# peripheral.net
KiCad netlist of a schematic drawn in Altium Designer
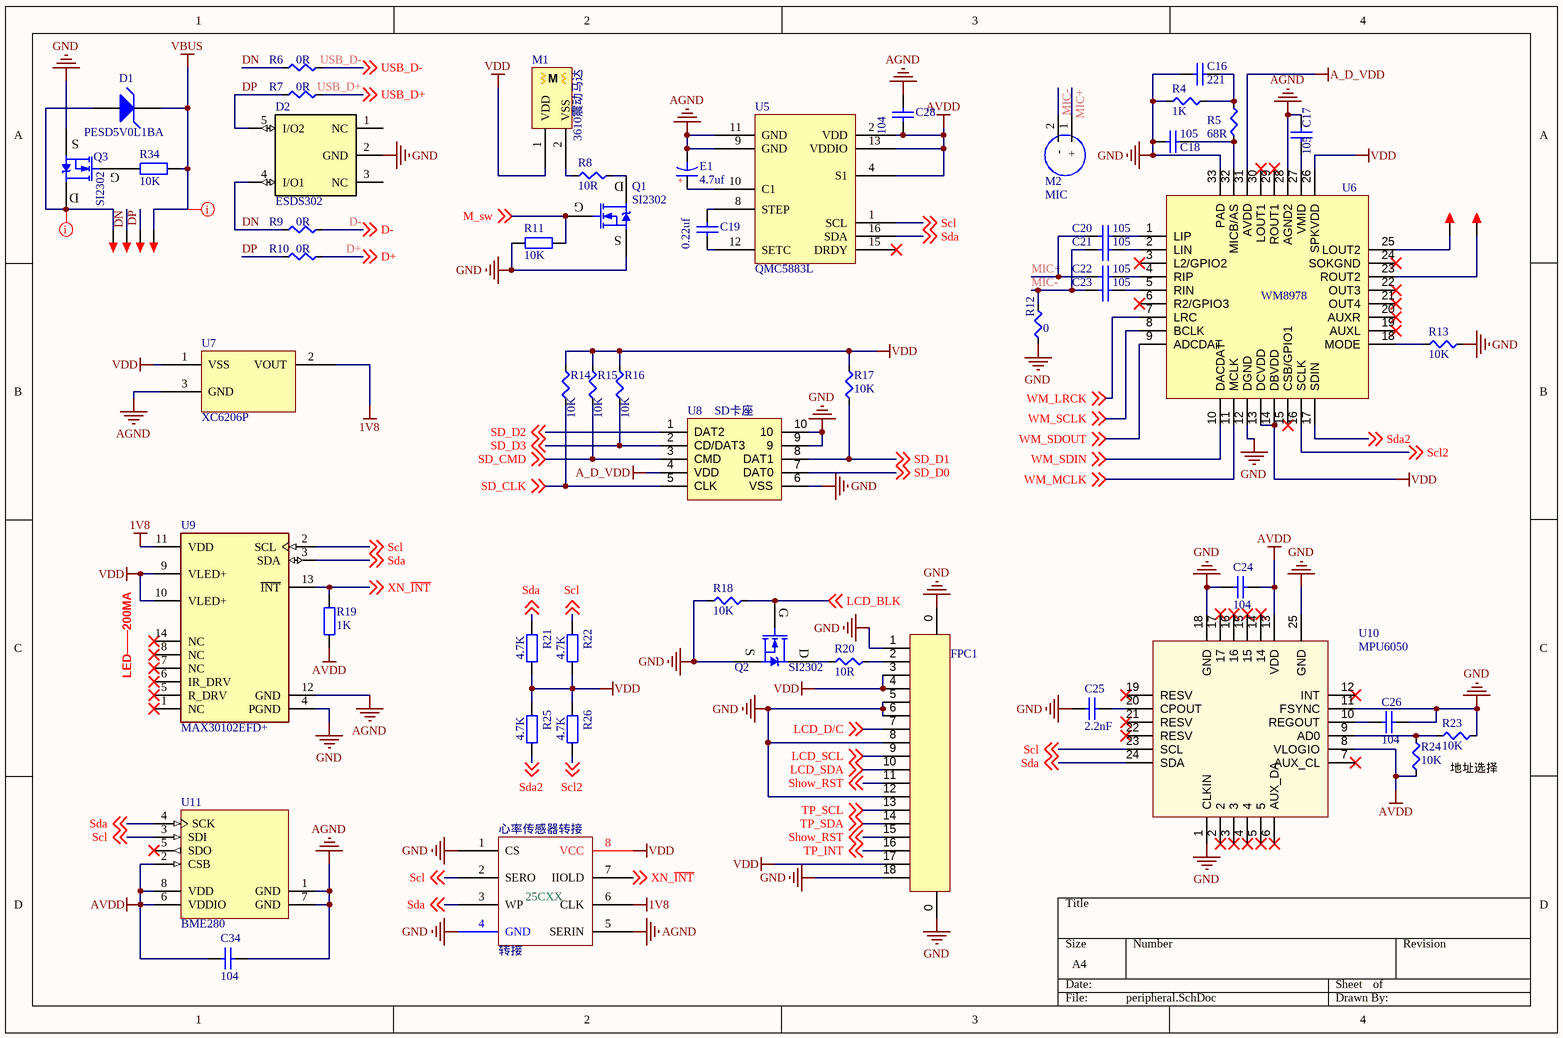
[diagram p0: peripheral.SchDoc]

(export (version "E")
  (design (tool "Eeschema 10.0.6"))
  (components
    (comp (ref "C16")
      (value "221")
      (footprint "C 0603_L")
      (description "贴片电容")
      (libsource (lib "0.1 - 电阻-电容-电感") (part "C"))
    )
    (comp (ref "C17")
      (value "105")
      (footprint "C 0603_L")
      (description "贴片电容")
      (libsource (lib "0.1 - 电阻-电容-电感") (part "C"))
    )
    (comp (ref "C18")
      (value "105")
      (footprint "C 0603_L")
      (description "贴片电容")
      (libsource (lib "0.1 - 电阻-电容-电感") (part "C"))
    )
    (comp (ref "C19")
      (value "0.22uf")
      (footprint "C 0603_L")
      (description "贴片电容")
      (libsource (lib "0.1 - 电阻-电容-电感") (part "C"))
    )
    (comp (ref "C20")
      (value "105")
      (footprint "C 0603_L")
      (description "贴片电容")
      (libsource (lib "0.1 - 电阻-电容-电感") (part "C"))
    )
    (comp (ref "C21")
      (value "105")
      (footprint "C 0603_L")
      (description "贴片电容")
      (libsource (lib "0.1 - 电阻-电容-电感") (part "C"))
    )
    (comp (ref "C22")
      (value "105")
      (footprint "C 0603_L")
      (description "贴片电容")
      (libsource (lib "0.1 - 电阻-电容-电感") (part "C"))
    )
    (comp (ref "C23")
      (value "105")
      (footprint "C 0603_L")
      (description "贴片电容")
      (libsource (lib "0.1 - 电阻-电容-电感") (part "C"))
    )
    (comp (ref "C24")
      (value "104")
      (footprint "C 0603_L")
      (description "贴片电容")
      (libsource (lib "0.1 - 电阻-电容-电感") (part "C"))
    )
    (comp (ref "C25")
      (value "2.2nF")
      (footprint "C 0603_L")
      (description "贴片电容")
      (libsource (lib "0.1 - 电阻-电容-电感") (part "C"))
    )
    (comp (ref "C26")
      (value "104")
      (footprint "C 0603_L")
      (description "贴片电容")
      (libsource (lib "0.1 - 电阻-电容-电感") (part "C"))
    )
    (comp (ref "C28")
      (value "104")
      (footprint "C 0603_L")
      (description "贴片电容")
      (libsource (lib "0.1 - 电阻-电容-电感") (part "C"))
    )
    (comp (ref "C34")
      (value "104")
      (footprint "C 0603_L")
      (description "贴片电容")
      (libsource (lib "0.1 - 电阻-电容-电感") (part "C"))
    )
    (comp (ref "D1")
      (value "PESD5V0L1BA")
      (footprint "SOD-323")
      (description "3.3v ESD")
      (libsource (lib "0.2 - 二极管-整流桥") (part "PESD3V3L1BA"))
    )
    (comp (ref "D2")
      (value "ESDS302")
      (footprint "SOT23-5")
      (description "USB2.0/Dual 2.3-pF, 3.6-V, ±30-kV")
      (libsource (lib "0.2 - 二极管-整流桥") (part "ESD"))
    )
    (comp (ref "E1")
      (value "4.7uf")
      (footprint "CD A(3216)")
      (description "贴片钽电容")
      (libsource (lib "0.1 - 电阻-电容-电感") (part "CT"))
    )
    (comp (ref "FPC1")
      (value "FPC")
      (footprint "FPC0.5 2H-WS-18P")
      (description "FPC 连接座,脚距0.5")
      (libsource (lib "FPC") (part "FPC18Pin"))
    )
    (comp (ref "M1") (value "3610震动马达") (libsource (lib "0.7 - 常用按键-开关-蜂鸣器-电池") (part "贴片震动电机3610")))
    (comp (ref "M2")
      (value "MIC")
      (footprint "驻极体电容咪头（ECM）")
      (description "驻极体电容咪头（ECM）φ4.5 x H2.2 mm")
      (libsource (lib "0.8 - 以太网-音频-USB插座") (part "MIC"))
    )
    (comp (ref "Q1")
      (value "SI2302")
      (footprint "SOT23-3N")
      (description "N沟道场效应管")
      (libsource (lib "0.4 - 三极管-场效应管-可控硅") (part "SI2302"))
    )
    (comp (ref "Q2")
      (value "SI2302")
      (footprint "SOT23-3N")
      (description "N沟道场效应管")
      (libsource (lib "0.4 - 三极管-场效应管-可控硅") (part "SI2302"))
    )
    (comp (ref "Q3")
      (value "SI2302")
      (footprint "SOT23-3N")
      (description "N沟道场效应管")
      (libsource (lib "0.4 - 三极管-场效应管-可控硅") (part "SI2302"))
    )
    (comp (ref "R4")
      (value "1K")
      (footprint "R 0603_L")
      (description "贴片电阻")
      (libsource (lib "0.1 - 电阻-电容-电感") (part "R"))
    )
    (comp (ref "R5")
      (value "68R")
      (footprint "R 0603_L")
      (description "贴片电阻")
      (libsource (lib "0.1 - 电阻-电容-电感") (part "R"))
    )
    (comp (ref "R6")
      (value "0R")
      (footprint "R 0603_L")
      (description "贴片电阻")
      (libsource (lib "0.1 - 电阻-电容-电感") (part "R"))
    )
    (comp (ref "R7")
      (value "0R")
      (footprint "R 0603_L")
      (description "贴片电阻")
      (libsource (lib "0.1 - 电阻-电容-电感") (part "R"))
    )
    (comp (ref "R8")
      (value "10R")
      (footprint "R 0603_L")
      (description "贴片电阻")
      (libsource (lib "0.1 - 电阻-电容-电感") (part "R"))
    )
    (comp (ref "R9")
      (value "0R")
      (footprint "R 0603_L")
      (description "贴片电阻")
      (libsource (lib "0.1 - 电阻-电容-电感") (part "R"))
    )
    (comp (ref "R10")
      (value "0R")
      (footprint "R 0603_L")
      (description "贴片电阻")
      (libsource (lib "0.1 - 电阻-电容-电感") (part "R"))
    )
    (comp (ref "R11")
      (value "10K")
      (footprint "R 0603_L")
      (description "贴片电阻")
      (libsource (lib "") (part "R_1"))
    )
    (comp (ref "R12")
      (value "0")
      (footprint "R 0603_L")
      (description "贴片电阻")
      (libsource (lib "0.1 - 电阻-电容-电感") (part "R"))
    )
    (comp (ref "R13")
      (value "10K")
      (footprint "R 0603_L")
      (description "贴片电阻")
      (libsource (lib "0.1 - 电阻-电容-电感") (part "R"))
    )
    (comp (ref "R14")
      (value "10K")
      (footprint "R 0603_L")
      (description "贴片电阻")
      (libsource (lib "0.1 - 电阻-电容-电感") (part "R"))
    )
    (comp (ref "R15")
      (value "10K")
      (footprint "R 0603_L")
      (description "贴片电阻")
      (libsource (lib "0.1 - 电阻-电容-电感") (part "R"))
    )
    (comp (ref "R16")
      (value "10K")
      (footprint "R 0603_L")
      (description "贴片电阻")
      (libsource (lib "0.1 - 电阻-电容-电感") (part "R"))
    )
    (comp (ref "R17")
      (value "10K")
      (footprint "R 0603_L")
      (description "贴片电阻")
      (libsource (lib "0.1 - 电阻-电容-电感") (part "R"))
    )
    (comp (ref "R18")
      (value "10K")
      (footprint "R 0603_L")
      (description "贴片电阻")
      (libsource (lib "0.1 - 电阻-电容-电感") (part "R"))
    )
    (comp (ref "R19")
      (value "1K")
      (footprint "R 0603_L")
      (description "贴片电阻")
      (libsource (lib "") (part "R_1"))
    )
    (comp (ref "R20")
      (value "10R")
      (footprint "R 0603_L")
      (description "贴片电阻")
      (libsource (lib "0.1 - 电阻-电容-电感") (part "R"))
    )
    (comp (ref "R21")
      (value "4.7K")
      (footprint "R 0603_L")
      (description "贴片电阻")
      (libsource (lib "") (part "R_1"))
    )
    (comp (ref "R22")
      (value "4.7K")
      (footprint "R 0603_L")
      (description "贴片电阻")
      (libsource (lib "") (part "R_1"))
    )
    (comp (ref "R23")
      (value "10K")
      (footprint "R 0603_L")
      (description "贴片电阻")
      (libsource (lib "0.1 - 电阻-电容-电感") (part "R"))
    )
    (comp (ref "R24")
      (value "10K")
      (footprint "R 0603_L")
      (description "贴片电阻")
      (libsource (lib "0.1 - 电阻-电容-电感") (part "R"))
    )
    (comp (ref "R25")
      (value "4.7K")
      (footprint "R 0603_L")
      (description "贴片电阻")
      (libsource (lib "") (part "R_1"))
    )
    (comp (ref "R26")
      (value "4.7K")
      (footprint "R 0603_L")
      (description "贴片电阻")
      (libsource (lib "") (part "R_1"))
    )
    (comp (ref "R34")
      (value "10K")
      (footprint "R 0603_L")
      (description "贴片电阻")
      (libsource (lib "") (part "R_1"))
    )
    (comp (ref "TP3")
      (value "TEST")
      (footprint "TEST 1")
      (description "测试点")
      (libsource (lib "0.7 - 常用按键-开关-蜂鸣器-电池") (part "TEST"))
    )
    (comp (ref "TP4")
      (value "TEST")
      (footprint "TEST 1")
      (description "测试点")
      (libsource (lib "0.7 - 常用按键-开关-蜂鸣器-电池") (part "TEST"))
    )
    (comp (ref "TP5")
      (value "TEST")
      (footprint "TEST 1")
      (description "测试点")
      (libsource (lib "0.7 - 常用按键-开关-蜂鸣器-电池") (part "TEST"))
    )
    (comp (ref "TP6")
      (value "TEST")
      (footprint "TEST 1")
      (description "测试点")
      (libsource (lib "0.7 - 常用按键-开关-蜂鸣器-电池") (part "TEST"))
    )
    (comp (ref "TP7")
      (value "TEST")
      (footprint "TEST 1")
      (description "测试点")
      (libsource (lib "0.7 - 常用按键-开关-蜂鸣器-电池") (part "TEST"))
    )
    (comp (ref "TP8")
      (value "TEST")
      (footprint "TEST 1")
      (description "测试点")
      (libsource (lib "0.7 - 常用按键-开关-蜂鸣器-电池") (part "TEST"))
    )
    (comp (ref "U5")
      (value "QMC5883L")
      (footprint "LGA-16_L3.0-W3.0-P0.50-BL_SQ")
      (description "三轴磁传感器")
      (libsource (lib "1.0 - 常见芯片") (part "QMC5883L"))
    )
    (comp (ref "U6")
      (value "WM8978")
      (footprint "QFN32-P50")
      (description "音频编解码芯片")
      (libsource (lib "1.0 - 常见芯片") (part "WM9878"))
    )
    (comp (ref "U7")
      (value "XC6206P")
      (footprint "SOT23")
      (description "最大输入电压：7V\r\n最大输出电流：200mA\r\n输入输出压差：200mV\r\n命名：（XC6205P）18代表1.8V")
      (libsource (lib "1.1 - 电源类芯片") (part "XC6206P"))
    )
    (comp (ref "U8")
      (value "SD卡座")
      (footprint "SD卡座")
      (description "SD卡座 简易短体式带壳")
      (libsource (lib "1.0 - 常见芯片") (part "SD卡座"))
    )
    (comp (ref "U9")
      (value "MAX30102EFD+")
      (footprint "FP-F143A5-1-MFG")
      (description "IC SENSOR OXIMETER/HEARTRATE")
      (fields
        (field (name "MANUFACTURER") "Maxim Integrated")
        (field (name "OCTOPART") "https://octopart.com/max30102efd%2B-maxim+integrated-59568799")
      )
      (libsource (lib "Altium Content Vault") (part "5fad416c1761f996ad02d0b395f9532"))
    )
    (comp (ref "U10")
      (value "MPU6050")
      (footprint "QFN24 4x4_N")
      (description "QFN24 4X4三轴加速度+三轴陀螺仪")
      (libsource (lib "1.0 - 常见芯片") (part "MPU6050"))
    )
    (comp (ref "U11")
      (value "BME280")
      (footprint "BOSC-BME280-8_V")
      (fields (field (name "MANUFACTURER") "Bosch Sensortec"))
      (libsource (lib "Altium Content Vault") (part "BOSC-BME280-8"))
    )
    (comp (ref "心率传感器转接") (value "转接") (footprint "SOP8改") (libsource (lib "1.0 - 常见芯片") (part "25CXX")))
  )
  (nets
    (net (code "1") (name "/DN") (class "Default")
      (node (ref "D2") (pin "4") (pinfunction "I/O1_4") (pintype "bidirectional"))
      (node (ref "R6") (pin "1") (pinfunction "1_1") (pintype "passive"))
      (node (ref "R9") (pin "1") (pinfunction "1_1") (pintype "passive"))
      (node (ref "TP7") (pin "1") (pinfunction "1_1") (pintype "passive"))
    )
    (net (code "2") (name "/DP") (class "Default")
      (node (ref "D2") (pin "5") (pinfunction "I/O2_5") (pintype "bidirectional"))
      (node (ref "R10") (pin "1") (pinfunction "1_1") (pintype "passive"))
      (node (ref "R7") (pin "1") (pinfunction "1_1") (pintype "passive"))
      (node (ref "TP4") (pin "1") (pinfunction "1_1") (pintype "passive"))
    )
    (net (code "3") (name "/MIC+") (class "Default")
      (node (ref "C20") (pin "1") (pinfunction "1_1") (pintype "passive"))
      (node (ref "C22") (pin "1") (pinfunction "1_1") (pintype "passive"))
      (node (ref "M2") (pin "1") (pinfunction "+_1") (pintype "passive"))
    )
    (net (code "4") (name "/MIC-") (class "Default")
      (node (ref "C21") (pin "1") (pinfunction "1_1") (pintype "passive"))
      (node (ref "C23") (pin "1") (pinfunction "1_1") (pintype "passive"))
      (node (ref "M2") (pin "2") (pinfunction "-_2") (pintype "passive"))
      (node (ref "R12") (pin "2") (pinfunction "2_2") (pintype "passive"))
    )
    (net (code "5") (name "1V8") (class "Default")
      (node (ref "U7") (pin "2") (pinfunction "VOUT_2") (pintype "power_in"))
      (node (ref "U9") (pin "11") (pinfunction "VDD_11") (pintype "power_in"))
      (node (ref "心率传感器转接") (pin "6") (pinfunction "CLK_6") (pintype "passive"))
    )
    (net (code "6") (name "AGND") (class "Default")
      (node (ref "C17") (pin "2") (pinfunction "2_2") (pintype "passive"))
      (node (ref "C28") (pin "2") (pinfunction "2_2") (pintype "passive"))
      (node (ref "C34") (pin "1") (pinfunction "1_1") (pintype "passive"))
      (node (ref "E1") (pin "2") (pinfunction "K_2") (pintype "passive"))
      (node (ref "U11") (pin "1") (pinfunction "GND_1") (pintype "power_in"))
      (node (ref "U11") (pin "7") (pinfunction "GND_7") (pintype "power_in"))
      (node (ref "U5") (pin "11") (pinfunction "GND_11") (pintype "passive"))
      (node (ref "U5") (pin "9") (pinfunction "GND_9") (pintype "power_in"))
      (node (ref "U6") (pin "28") (pinfunction "AGND2_28") (pintype "passive"))
      (node (ref "U7") (pin "3") (pinfunction "GND_3") (pintype "power_in"))
      (node (ref "U9") (pin "12") (pinfunction "GND_12") (pintype "power_in"))
      (node (ref "心率传感器转接") (pin "5") (pinfunction "SERIN_5") (pintype "passive"))
    )
    (net (code "7") (name "AVDD") (class "Default")
      (node (ref "C24") (pin "1") (pinfunction "1_1") (pintype "passive"))
      (node (ref "C28") (pin "1") (pinfunction "1_1") (pintype "passive"))
      (node (ref "C34") (pin "2") (pinfunction "2_2") (pintype "passive"))
      (node (ref "R19") (pin "1") (pinfunction "1_1") (pintype "passive"))
      (node (ref "R24") (pin "1") (pinfunction "1_1") (pintype "passive"))
      (node (ref "U10") (pin "13") (pinfunction "VDD_13") (pintype "passive"))
      (node (ref "U10") (pin "8") (pinfunction "VLOGIO_8") (pintype "passive"))
      (node (ref "U11") (pin "2") (pinfunction "CSB_2") (pintype "input"))
      (node (ref "U11") (pin "6") (pinfunction "VDDIO_6") (pintype "power_in"))
      (node (ref "U11") (pin "8") (pinfunction "VDD_8") (pintype "power_in"))
      (node (ref "U5") (pin "13") (pinfunction "VDDIO_13") (pintype "power_in"))
      (node (ref "U5") (pin "2") (pinfunction "VDD_2") (pintype "power_in"))
      (node (ref "U5") (pin "4") (pinfunction "S1_4") (pintype "passive"))
    )
    (net (code "8") (name "A_D_VDD") (class "Default")
      (node (ref "U6") (pin "31") (pinfunction "AVDD_31") (pintype "passive"))
      (node (ref "U8") (pin "4") (pinfunction "VDD_4") (pintype "passive"))
    )
    (net (code "9") (name "D+") (class "Default")
      (node (ref "R10") (pin "2") (pinfunction "2_2") (pintype "passive"))
    )
    (net (code "10") (name "D-") (class "Default")
      (node (ref "R9") (pin "2") (pinfunction "2_2") (pintype "passive"))
    )
    (net (code "11") (name "GND") (class "Default")
      (node (ref "C16") (pin "1") (pinfunction "1_1") (pintype "passive"))
      (node (ref "C18") (pin "1") (pinfunction "1_1") (pintype "passive"))
      (node (ref "C24") (pin "2") (pinfunction "2_2") (pintype "passive"))
      (node (ref "C25") (pin "2") (pinfunction "2_2") (pintype "passive"))
      (node (ref "C26") (pin "1") (pinfunction "1_1") (pintype "passive"))
      (node (ref "D2") (pin "2") (pinfunction "GND_2") (pintype "power_in"))
      (node (ref "FPC1") (pin "0") (pinfunction "0_0") (pintype "passive"))
      (node (ref "FPC1") (pin "1") (pintype "passive"))
      (node (ref "FPC1") (pin "12") (pintype "passive"))
      (node (ref "FPC1") (pin "18") (pintype "passive"))
      (node (ref "FPC1") (pin "5") (pintype "passive"))
      (node (ref "FPC1") (pin "6") (pintype "passive"))
      (node (ref "FPC1") (pin "8") (pintype "passive"))
      (node (ref "Q1") (pin "2") (pinfunction "S_2") (pintype "passive"))
      (node (ref "Q2") (pin "2") (pinfunction "S_2") (pintype "passive"))
      (node (ref "Q3") (pin "2") (pinfunction "S_2") (pintype "passive"))
      (node (ref "R11") (pin "1") (pinfunction "1_1") (pintype "passive"))
      (node (ref "R12") (pin "1") (pinfunction "1_1") (pintype "passive"))
      (node (ref "R13") (pin "2") (pinfunction "2_2") (pintype "passive"))
      (node (ref "R18") (pin "1") (pinfunction "1_1") (pintype "passive"))
      (node (ref "R23") (pin "2") (pinfunction "2_2") (pintype "passive"))
      (node (ref "R4") (pin "1") (pinfunction "1_1") (pintype "passive"))
      (node (ref "U10") (pin "1") (pinfunction "CLKIN_1") (pintype "passive"))
      (node (ref "U10") (pin "11") (pinfunction "FSYNC_11") (pintype "passive"))
      (node (ref "U10") (pin "18") (pinfunction "GND_18") (pintype "passive"))
      (node (ref "U10") (pin "25") (pinfunction "GND_25") (pintype "passive"))
      (node (ref "U6") (pin "12") (pinfunction "DGND_12") (pintype "passive"))
      (node (ref "U6") (pin "33") (pinfunction "PAD_33") (pintype "passive"))
      (node (ref "U8") (pin "10") (pinfunction "10_10") (pintype "passive"))
      (node (ref "U8") (pin "6") (pinfunction "VSS_6") (pintype "passive"))
      (node (ref "U8") (pin "9") (pinfunction "9_9") (pintype "passive"))
      (node (ref "U9") (pin "4") (pinfunction "PGND_4") (pintype "power_in"))
      (node (ref "心率传感器转接") (pin "1") (pinfunction "CS_1") (pintype "passive"))
      (node (ref "心率传感器转接") (pin "4") (pinfunction "GND_4") (pintype "passive"))
    )
    (net (code "12") (name "LCD_BLK") (class "Default")
      (node (ref "Q2") (pin "1") (pinfunction "G_1") (pintype "passive"))
      (node (ref "R18") (pin "2") (pinfunction "2_2") (pintype "passive"))
    )
    (net (code "13") (name "LCD_D{slash}C") (class "Default")
      (node (ref "FPC1") (pin "7") (pintype "passive"))
    )
    (net (code "14") (name "LCD_SCL") (class "Default") (node (ref "FPC1") (pin "9") (pintype "passive")))
    (net (code "15") (name "LCD_SDA") (class "Default") (node (ref "FPC1") (pin "10") (pintype "passive")))
    (net (code "16") (name "M_sw") (class "Default")
      (node (ref "Q1") (pin "1") (pinfunction "G_1") (pintype "passive"))
      (node (ref "R11") (pin "2") (pinfunction "2_2") (pintype "passive"))
    )
    (net (code "17") (name "Net-(C16-Pad2)") (class "Default")
      (node (ref "C16") (pin "2") (pinfunction "2_2") (pintype "passive"))
      (node (ref "R4") (pin "2") (pinfunction "2_2") (pintype "passive"))
      (node (ref "R5") (pin "2") (pinfunction "2_2") (pintype "passive"))
    )
    (net (code "18") (name "Net-(D1-A)") (class "Default")
      (node (ref "D1") (pin "1") (pinfunction "A_1") (pintype "passive"))
      (node (ref "Q3") (pin "3") (pinfunction "D_3") (pintype "passive"))
      (node (ref "TP3") (pin "1") (pinfunction "1_1") (pintype "passive"))
    )
    (net (code "19") (name "Net-(E1-A)") (class "Default")
      (node (ref "E1") (pin "1") (pinfunction "A_1") (pintype "passive"))
      (node (ref "U5") (pin "10") (pinfunction "C1_10") (pintype "passive"))
    )
    (net (code "20") (name "Net-(FPC1-Pad2)") (class "Default")
      (node (ref "FPC1") (pin "2") (pintype "passive"))
      (node (ref "R20") (pin "2") (pinfunction "2_2") (pintype "passive"))
    )
    (net (code "21") (name "Net-(M1-VSS)") (class "Default")
      (node (ref "M1") (pin "2") (pinfunction "VSS_2") (pintype "power_in"))
      (node (ref "R8") (pin "1") (pinfunction "1_1") (pintype "passive"))
    )
    (net (code "22") (name "Net-(Q1-D)") (class "Default")
      (node (ref "Q1") (pin "3") (pinfunction "D_3") (pintype "passive"))
      (node (ref "R8") (pin "2") (pinfunction "2_2") (pintype "passive"))
    )
    (net (code "23") (name "Net-(Q2-D)") (class "Default")
      (node (ref "Q2") (pin "3") (pinfunction "D_3") (pintype "passive"))
      (node (ref "R20") (pin "1") (pinfunction "1_1") (pintype "passive"))
    )
    (net (code "24") (name "Net-(Q3-G)") (class "Default")
      (node (ref "Q3") (pin "1") (pinfunction "G_1") (pintype "passive"))
      (node (ref "R34") (pin "1") (pinfunction "1_1") (pintype "passive"))
    )
    (net (code "25") (name "Net-(U5-SETC)") (class "Default")
      (node (ref "C19") (pin "1") (pinfunction "1_1") (pintype "passive"))
      (node (ref "U5") (pin "12") (pinfunction "SETC_12") (pintype "passive"))
    )
    (net (code "26") (name "Net-(U5-STEP)") (class "Default")
      (node (ref "C19") (pin "2") (pinfunction "2_2") (pintype "passive"))
      (node (ref "U5") (pin "8") (pinfunction "STEP_8") (pintype "passive"))
    )
    (net (code "27") (name "Net-(U6-LIN)") (class "Default")
      (node (ref "C21") (pin "2") (pinfunction "2_2") (pintype "passive"))
      (node (ref "U6") (pin "2") (pinfunction "LIN_2") (pintype "passive"))
    )
    (net (code "28") (name "Net-(U6-LIP)") (class "Default")
      (node (ref "C20") (pin "2") (pinfunction "2_2") (pintype "passive"))
      (node (ref "U6") (pin "1") (pinfunction "LIP_1") (pintype "passive"))
    )
    (net (code "29") (name "Net-(U6-LOUT2)") (class "Default")
      (node (ref "TP5") (pin "1") (pinfunction "1_1") (pintype "passive"))
      (node (ref "U6") (pin "25") (pinfunction "LOUT2_25") (pintype "passive"))
    )
    (net (code "30") (name "Net-(U6-MICB{slash}AS)") (class "Default")
      (node (ref "C18") (pin "2") (pinfunction "2_2") (pintype "passive"))
      (node (ref "R5") (pin "1") (pinfunction "1_1") (pintype "passive"))
      (node (ref "U6") (pin "32") (pinfunction "MICB/AS_32") (pintype "passive"))
    )
    (net (code "31") (name "Net-(U6-MODE)") (class "Default")
      (node (ref "R13") (pin "1") (pinfunction "1_1") (pintype "passive"))
      (node (ref "U6") (pin "18") (pinfunction "MODE_18") (pintype "passive"))
    )
    (net (code "32") (name "Net-(U6-RIN)") (class "Default")
      (node (ref "C23") (pin "2") (pinfunction "2_2") (pintype "passive"))
      (node (ref "U6") (pin "5") (pinfunction "RIN_5") (pintype "passive"))
    )
    (net (code "33") (name "Net-(U6-RIP)") (class "Default")
      (node (ref "C22") (pin "2") (pinfunction "2_2") (pintype "passive"))
      (node (ref "U6") (pin "4") (pinfunction "RIP_4") (pintype "passive"))
    )
    (net (code "34") (name "Net-(U6-ROUT2)") (class "Default")
      (node (ref "TP6") (pin "1") (pinfunction "1_1") (pintype "passive"))
      (node (ref "U6") (pin "23") (pinfunction "ROUT2_23") (pintype "passive"))
    )
    (net (code "35") (name "Net-(U6-VMID)") (class "Default")
      (node (ref "C17") (pin "1") (pinfunction "1_1") (pintype "passive"))
      (node (ref "U6") (pin "27") (pinfunction "VMID_27") (pintype "passive"))
    )
    (net (code "36") (name "Net-(U10-AD0)") (class "Default")
      (node (ref "R23") (pin "1") (pinfunction "1_1") (pintype "passive"))
      (node (ref "R24") (pin "2") (pinfunction "2_2") (pintype "passive"))
      (node (ref "U10") (pin "9") (pinfunction "AD0_9") (pintype "passive"))
    )
    (net (code "37") (name "Net-(U10-CPOUT)") (class "Default")
      (node (ref "C25") (pin "1") (pinfunction "1_1") (pintype "passive"))
      (node (ref "U10") (pin "20") (pinfunction "CPOUT_20") (pintype "passive"))
    )
    (net (code "38") (name "Net-(U10-REGOUT)") (class "Default")
      (node (ref "C26") (pin "2") (pinfunction "2_2") (pintype "passive"))
      (node (ref "U10") (pin "10") (pinfunction "REGOUT_10") (pintype "passive"))
    )
    (net (code "39") (name "SD_CLK") (class "Default")
      (node (ref "R14") (pin "1") (pinfunction "1_1") (pintype "passive"))
      (node (ref "U8") (pin "5") (pinfunction "CLK_5") (pintype "passive"))
    )
    (net (code "40") (name "SD_CMD") (class "Default")
      (node (ref "R15") (pin "1") (pinfunction "1_1") (pintype "passive"))
      (node (ref "U8") (pin "3") (pinfunction "CMD_3") (pintype "passive"))
    )
    (net (code "41") (name "SD_D0") (class "Default")
      (node (ref "U8") (pin "7") (pinfunction "DAT0_7") (pintype "passive"))
    )
    (net (code "42") (name "SD_D1") (class "Default")
      (node (ref "R17") (pin "1") (pinfunction "1_1") (pintype "passive"))
      (node (ref "U8") (pin "8") (pinfunction "DAT1_8") (pintype "passive"))
    )
    (net (code "43") (name "SD_D2") (class "Default")
      (node (ref "U8") (pin "1") (pinfunction "DAT2_1") (pintype "passive"))
    )
    (net (code "44") (name "SD_D3") (class "Default")
      (node (ref "R16") (pin "1") (pinfunction "1_1") (pintype "passive"))
      (node (ref "U8") (pin "2") (pinfunction "CD/DAT3_2") (pintype "passive"))
    )
    (net (code "45") (name "Scl") (class "Default")
      (node (ref "R22") (pin "1") (pinfunction "1_1") (pintype "passive"))
      (node (ref "U10") (pin "23") (pinfunction "SCL_23") (pintype "passive"))
      (node (ref "U11") (pin "3") (pinfunction "SDI_3") (pintype "input"))
      (node (ref "U5") (pin "1") (pinfunction "SCL_1") (pintype "passive"))
      (node (ref "U9") (pin "2") (pinfunction "SCL_2") (pintype "input"))
      (node (ref "心率传感器转接") (pin "2") (pinfunction "SERO_2") (pintype "passive"))
    )
    (net (code "46") (name "Scl2") (class "Default")
      (node (ref "R26") (pin "2") (pinfunction "2_2") (pintype "passive"))
      (node (ref "U6") (pin "16") (pinfunction "SCLK_16") (pintype "passive"))
    )
    (net (code "47") (name "Sda") (class "Default")
      (node (ref "R21") (pin "1") (pinfunction "1_1") (pintype "passive"))
      (node (ref "U10") (pin "24") (pinfunction "SDA_24") (pintype "passive"))
      (node (ref "U11") (pin "4") (pinfunction "SCK_4") (pintype "input"))
      (node (ref "U5") (pin "16") (pinfunction "SDA_16") (pintype "passive"))
      (node (ref "U9") (pin "3") (pinfunction "SDA_3") (pintype "bidirectional"))
      (node (ref "心率传感器转接") (pin "3") (pinfunction "WP_3") (pintype "passive"))
    )
    (net (code "48") (name "Sda2") (class "Default")
      (node (ref "R25") (pin "2") (pinfunction "2_2") (pintype "passive"))
      (node (ref "U6") (pin "17") (pinfunction "SDIN_17") (pintype "passive"))
    )
    (net (code "49") (name "Show_RST") (class "Default")
      (node (ref "FPC1") (pin "11") (pintype "passive"))
      (node (ref "FPC1") (pin "15") (pintype "passive"))
    )
    (net (code "50") (name "TP_INT") (class "Default") (node (ref "FPC1") (pin "16") (pintype "passive")))
    (net (code "51") (name "TP_SCL") (class "Default") (node (ref "FPC1") (pin "13") (pintype "passive")))
    (net (code "52") (name "TP_SDA") (class "Default") (node (ref "FPC1") (pin "14") (pintype "passive")))
    (net (code "53") (name "USB_D+") (class "Default")
      (node (ref "R7") (pin "2") (pinfunction "2_2") (pintype "passive"))
    )
    (net (code "54") (name "USB_D-") (class "Default")
      (node (ref "R6") (pin "2") (pinfunction "2_2") (pintype "passive"))
    )
    (net (code "55") (name "VBUS") (class "Default")
      (node (ref "D1") (pin "2") (pinfunction "K_2") (pintype "passive"))
      (node (ref "R34") (pin "2") (pinfunction "2_2") (pintype "passive"))
      (node (ref "TP8") (pin "1") (pinfunction "1_1") (pintype "passive"))
    )
    (net (code "56") (name "VDD") (class "Default")
      (node (ref "FPC1") (pin "17") (pintype "passive"))
      (node (ref "FPC1") (pin "3") (pintype "passive"))
      (node (ref "FPC1") (pin "4") (pintype "passive"))
      (node (ref "M1") (pin "1") (pinfunction "VDD_1") (pintype "power_in"))
      (node (ref "R14") (pin "2") (pinfunction "2_2") (pintype "passive"))
      (node (ref "R15") (pin "2") (pinfunction "2_2") (pintype "passive"))
      (node (ref "R16") (pin "2") (pinfunction "2_2") (pintype "passive"))
      (node (ref "R17") (pin "2") (pinfunction "2_2") (pintype "passive"))
      (node (ref "R21") (pin "2") (pinfunction "2_2") (pintype "passive"))
      (node (ref "R22") (pin "2") (pinfunction "2_2") (pintype "passive"))
      (node (ref "R25") (pin "1") (pinfunction "1_1") (pintype "passive"))
      (node (ref "R26") (pin "1") (pinfunction "1_1") (pintype "passive"))
      (node (ref "U6") (pin "13") (pinfunction "DCVDD_13") (pintype "passive"))
      (node (ref "U6") (pin "14") (pinfunction "DBVDD_14") (pintype "passive"))
      (node (ref "U6") (pin "26") (pinfunction "SPKVDD_26") (pintype "passive"))
      (node (ref "U7") (pin "1") (pinfunction "VSS_1") (pintype "power_in"))
      (node (ref "U9") (pin "10") (pinfunction "VLED+_10") (pintype "power_in"))
      (node (ref "U9") (pin "9") (pinfunction "VLED+_9") (pintype "power_in"))
      (node (ref "心率传感器转接") (pin "8") (pinfunction "VCC_8") (pintype "passive"))
    )
    (net (code "57") (name "WM_LRCK") (class "Default")
      (node (ref "U6") (pin "7") (pinfunction "LRC_7") (pintype "passive"))
    )
    (net (code "58") (name "WM_MCLK") (class "Default")
      (node (ref "U6") (pin "11") (pinfunction "MCLK_11") (pintype "passive"))
    )
    (net (code "59") (name "WM_SCLK") (class "Default")
      (node (ref "U6") (pin "8") (pinfunction "BCLK_8") (pintype "passive"))
    )
    (net (code "60") (name "WM_SDIN") (class "Default")
      (node (ref "U6") (pin "10") (pinfunction "DACDAT_10") (pintype "passive"))
    )
    (net (code "61") (name "WM_SDOUT") (class "Default")
      (node (ref "U6") (pin "9") (pinfunction "ADCDAT_9") (pintype "passive"))
    )
    (net (code "62") (name "XN_~{INT}") (class "Default")
      (node (ref "R19") (pin "2") (pinfunction "2_2") (pintype "passive"))
      (node (ref "U9") (pin "13") (pinfunction "~{INT}_13") (pintype "open_collector"))
      (node (ref "心率传感器转接") (pin "7") (pinfunction "IIOLD_7") (pintype "passive"))
    )
    (net (code "63") (name "unconnected-(D2-NC-Pad1)") (class "Default")
      (node (ref "D2") (pin "1") (pinfunction "NC_1") (pintype "passive"))
    )
    (net (code "64") (name "unconnected-(D2-NC-Pad3)") (class "Default")
      (node (ref "D2") (pin "3") (pinfunction "NC_3") (pintype "passive"))
    )
    (net (code "65") (name "unconnected-(U5-DRDY-Pad15)") (class "Default")
      (node (ref "U5") (pin "15") (pinfunction "DRDY_15") (pintype "passive+no_connect"))
    )
    (net (code "66") (name "unconnected-(U6-AUXL-Pad19)") (class "Default")
      (node (ref "U6") (pin "19") (pinfunction "AUXL_19") (pintype "passive+no_connect"))
    )
    (net (code "67") (name "unconnected-(U6-AUXR-Pad20)") (class "Default")
      (node (ref "U6") (pin "20") (pinfunction "AUXR_20") (pintype "passive+no_connect"))
    )
    (net (code "68") (name "unconnected-(U6-CSB{slash}GPIO1-Pad15)") (class "Default")
      (node (ref "U6") (pin "15") (pinfunction "CSB/GPIO1_15") (pintype "passive+no_connect"))
    )
    (net (code "69") (name "unconnected-(U6-L2{slash}GPIO2-Pad3)") (class "Default")
      (node (ref "U6") (pin "3") (pinfunction "L2/GPIO2_3") (pintype "passive+no_connect"))
    )
    (net (code "70") (name "unconnected-(U6-LOUT1-Pad30)") (class "Default")
      (node (ref "U6") (pin "30") (pinfunction "LOUT1_30") (pintype "passive+no_connect"))
    )
    (net (code "71") (name "unconnected-(U6-OUT3-Pad22)") (class "Default")
      (node (ref "U6") (pin "22") (pinfunction "OUT3_22") (pintype "passive+no_connect"))
    )
    (net (code "72") (name "unconnected-(U6-OUT4-Pad21)") (class "Default")
      (node (ref "U6") (pin "21") (pinfunction "OUT4_21") (pintype "passive+no_connect"))
    )
    (net (code "73") (name "unconnected-(U6-R2{slash}GPIO3-Pad6)") (class "Default")
      (node (ref "U6") (pin "6") (pinfunction "R2/GPIO3_6") (pintype "passive+no_connect"))
    )
    (net (code "74") (name "unconnected-(U6-ROUT1-Pad29)") (class "Default")
      (node (ref "U6") (pin "29") (pinfunction "ROUT1_29") (pintype "passive+no_connect"))
    )
    (net (code "75") (name "unconnected-(U6-SOKGND-Pad24)") (class "Default")
      (node (ref "U6") (pin "24") (pinfunction "SOKGND_24") (pintype "passive+no_connect"))
    )
    (net (code "76") (name "unconnected-(U9-IR_DRV-Pad6)") (class "Default")
      (node (ref "U9") (pin "6") (pinfunction "IR_DRV_6") (pintype "passive+no_connect"))
    )
    (net (code "77") (name "unconnected-(U9-NC-Pad1)") (class "Default")
      (node (ref "U9") (pin "1") (pinfunction "NC_1") (pintype "passive+no_connect"))
    )
    (net (code "78") (name "unconnected-(U9-NC-Pad7)") (class "Default")
      (node (ref "U9") (pin "7") (pinfunction "NC_7") (pintype "passive+no_connect"))
    )
    (net (code "79") (name "unconnected-(U9-NC-Pad8)") (class "Default")
      (node (ref "U9") (pin "8") (pinfunction "NC_8") (pintype "passive+no_connect"))
    )
    (net (code "80") (name "unconnected-(U9-NC-Pad14)") (class "Default")
      (node (ref "U9") (pin "14") (pinfunction "NC_14") (pintype "passive+no_connect"))
    )
    (net (code "81") (name "unconnected-(U9-R_DRV-Pad5)") (class "Default")
      (node (ref "U9") (pin "5") (pinfunction "R_DRV_5") (pintype "passive+no_connect"))
    )
    (net (code "82") (name "unconnected-(U10-AUX_CL-Pad7)") (class "Default")
      (node (ref "U10") (pin "7") (pinfunction "AUX_CL_7") (pintype "passive+no_connect"))
    )
    (net (code "83") (name "unconnected-(U10-AUX_DA-Pad6)") (class "Default")
      (node (ref "U10") (pin "6") (pinfunction "AUX_DA_6") (pintype "passive+no_connect"))
    )
    (net (code "84") (name "unconnected-(U10-INT-Pad12)") (class "Default")
      (node (ref "U10") (pin "12") (pinfunction "INT_12") (pintype "passive+no_connect"))
    )
    (net (code "85") (name "unconnected-(U10-Pad2)") (class "Default")
      (node (ref "U10") (pin "2") (pinfunction "2_2") (pintype "passive+no_connect"))
    )
    (net (code "86") (name "unconnected-(U10-Pad3)") (class "Default")
      (node (ref "U10") (pin "3") (pinfunction "3_3") (pintype "passive+no_connect"))
    )
    (net (code "87") (name "unconnected-(U10-Pad4)") (class "Default")
      (node (ref "U10") (pin "4") (pinfunction "4_4") (pintype "passive+no_connect"))
    )
    (net (code "88") (name "unconnected-(U10-Pad5)") (class "Default")
      (node (ref "U10") (pin "5") (pinfunction "5_5") (pintype "passive+no_connect"))
    )
    (net (code "89") (name "unconnected-(U10-Pad14)") (class "Default")
      (node (ref "U10") (pin "14") (pinfunction "14_14") (pintype "passive+no_connect"))
    )
    (net (code "90") (name "unconnected-(U10-Pad15)") (class "Default")
      (node (ref "U10") (pin "15") (pinfunction "15_15") (pintype "passive+no_connect"))
    )
    (net (code "91") (name "unconnected-(U10-Pad16)") (class "Default")
      (node (ref "U10") (pin "16") (pinfunction "16_16") (pintype "passive+no_connect"))
    )
    (net (code "92") (name "unconnected-(U10-Pad17)") (class "Default")
      (node (ref "U10") (pin "17") (pinfunction "17_17") (pintype "passive+no_connect"))
    )
    (net (code "93") (name "unconnected-(U10-RESV-Pad19)") (class "Default")
      (node (ref "U10") (pin "19") (pinfunction "RESV_19") (pintype "passive+no_connect"))
    )
    (net (code "94") (name "unconnected-(U10-RESV-Pad21)") (class "Default")
      (node (ref "U10") (pin "21") (pinfunction "RESV_21") (pintype "passive+no_connect"))
    )
    (net (code "95") (name "unconnected-(U10-RESV-Pad22)") (class "Default")
      (node (ref "U10") (pin "22") (pinfunction "RESV_22") (pintype "passive+no_connect"))
    )
    (net (code "96") (name "unconnected-(U11-SDO-Pad5)") (class "Default")
      (node (ref "U11") (pin "5") (pinfunction "SDO_5") (pintype "output+no_connect"))
    )
  )
)
